# C-02_LvDDR3.net
KiCad netlist of a schematic drawn in Altium Designer
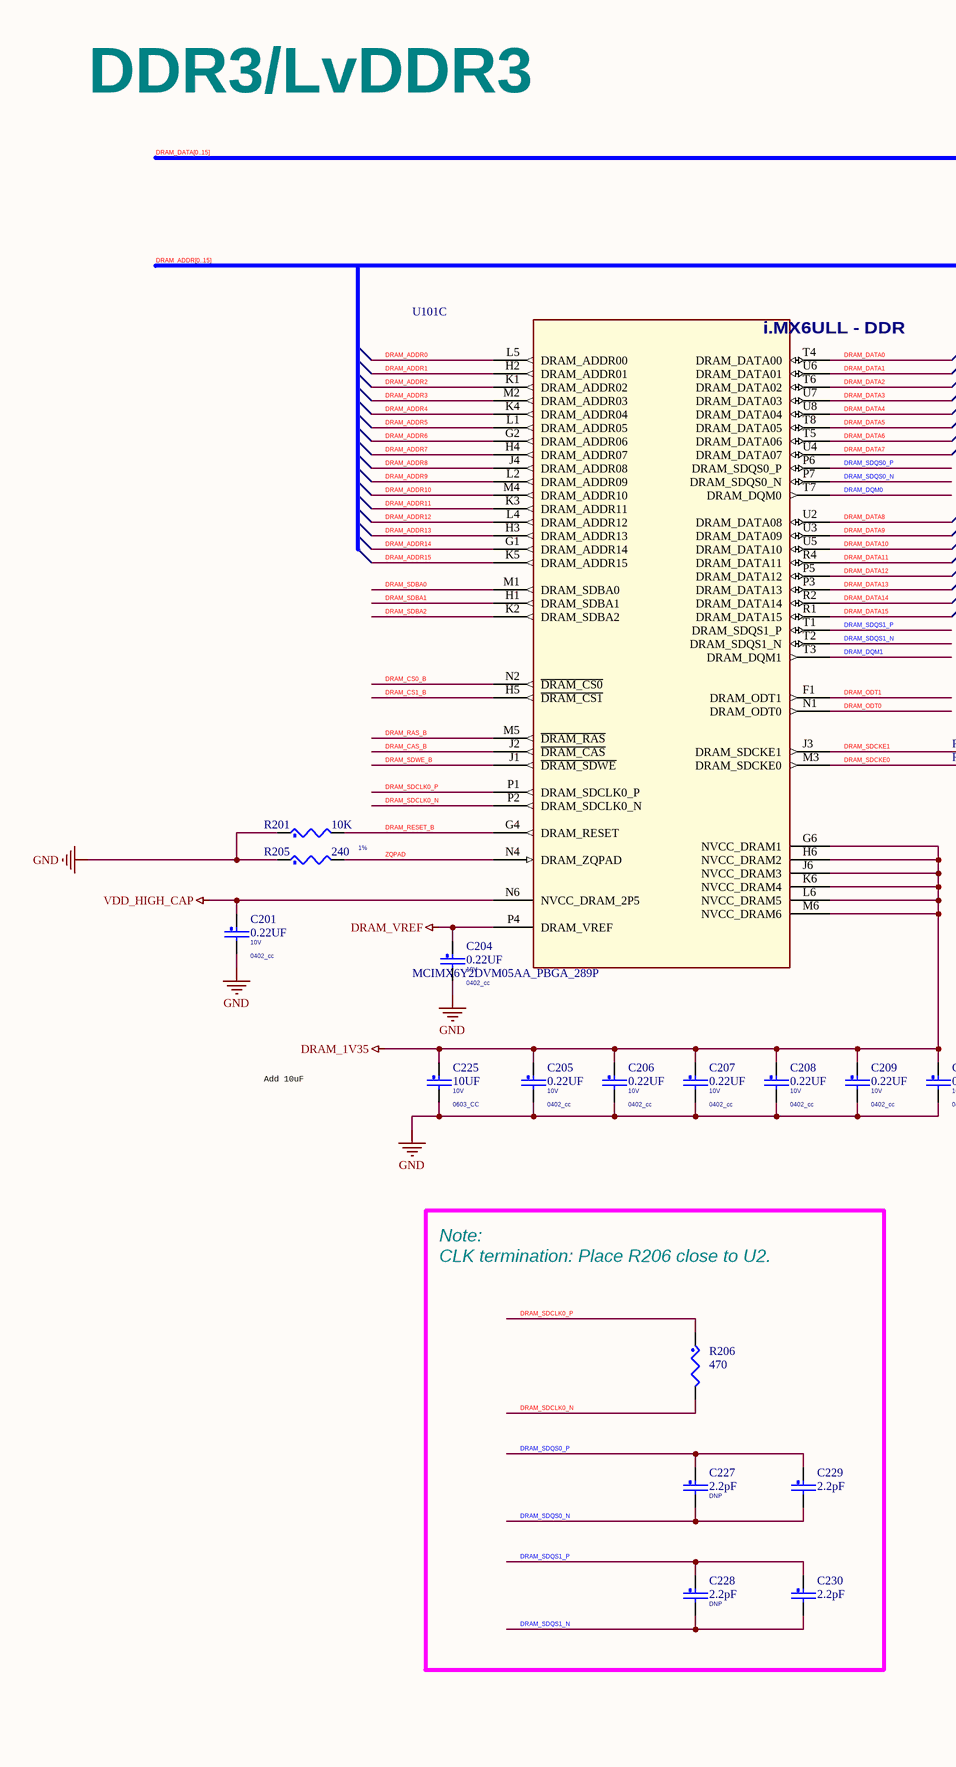
[diagram p0: C-02 LvDDR3.SchDoc, left]
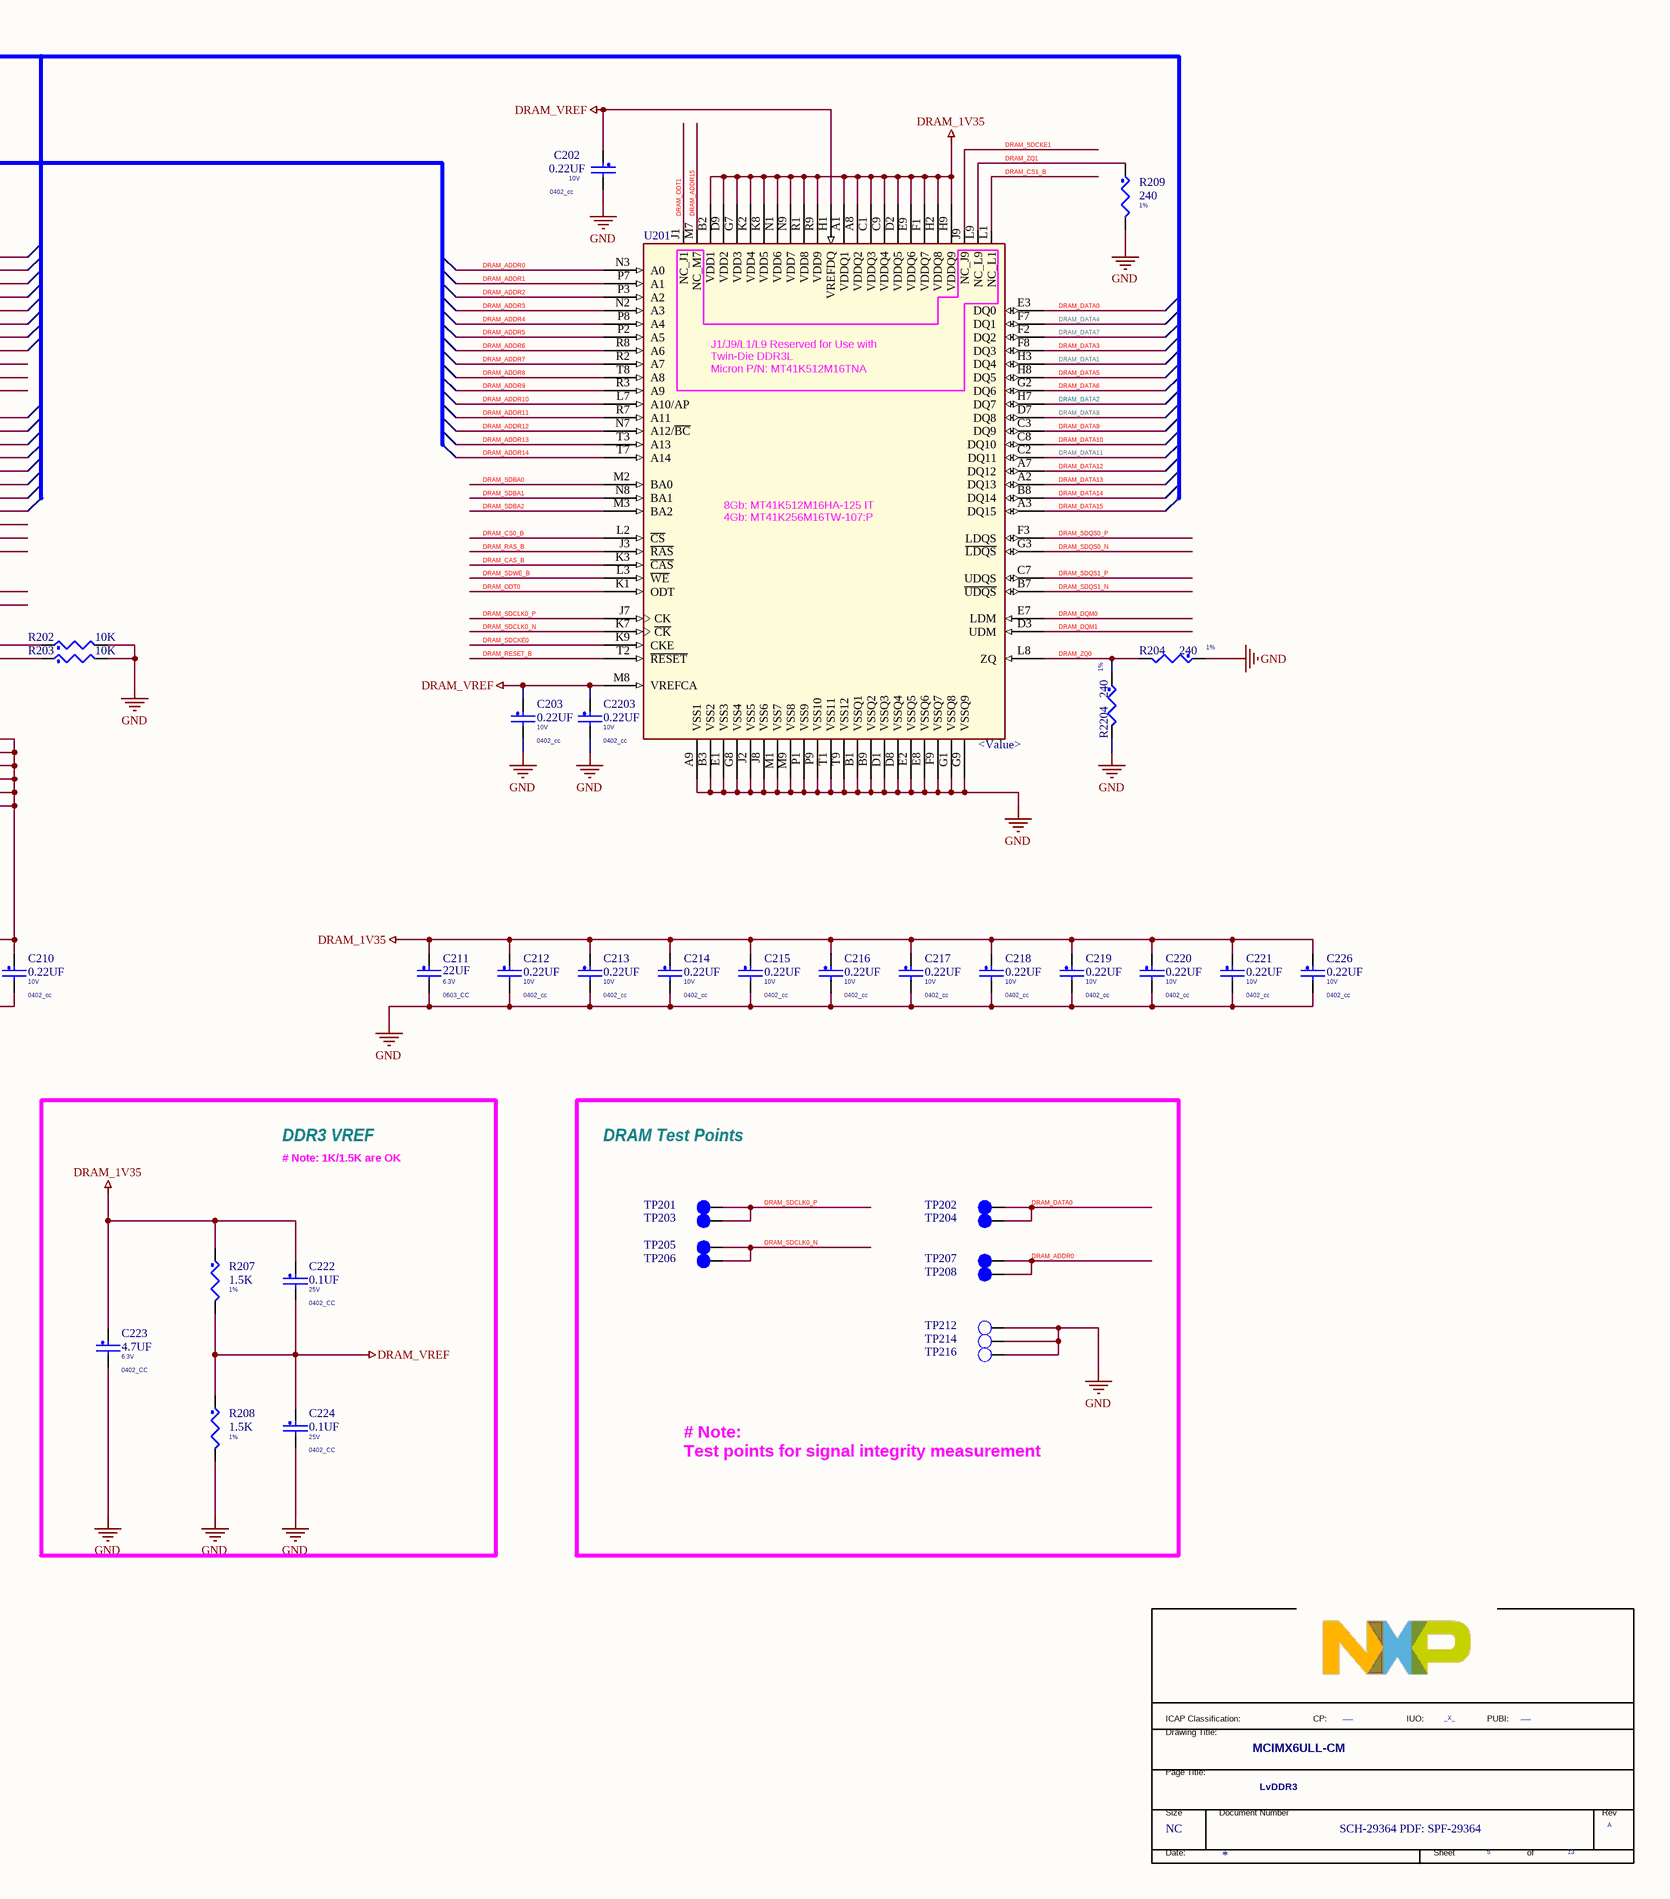
[diagram p1: C-02 LvDDR3.SchDoc, right]

(export (version "E")
  (design (tool "Eeschema 10.0.6"))
  (components
    (comp (ref "C201")
      (value "0.22UF")
      (footprint "C0402_H0.5mm")
      (description "CAP CER 0.22UF 10V 10% X5R 0402")
      (fields
        (field (name "TOLERANCE") "10%")
        (field (name "VOLTAGE") "10V")
        (field (name "PCB FOOTPRINT") "0402_cc")
      )
      (libsource (lib "*") (part "CAP_NP"))
    )
    (comp (ref "C202")
      (value "0.22UF")
      (footprint "C0402_H0.5mm")
      (description "CAP CER 0.22UF 10V 10% X5R 0402")
      (fields
        (field (name "VOLTAGE") "10V")
        (field (name "TOLERANCE") "10%")
        (field (name "PCB FOOTPRINT") "0402_cc")
      )
      (libsource (lib "*") (part "CAP_NP"))
    )
    (comp (ref "C203")
      (value "0.22UF")
      (footprint "C0402_H0.5mm")
      (description "CAP CER 0.22UF 10V 10% X5R 0402")
      (fields
        (field (name "VOLTAGE") "10V")
        (field (name "TOLERANCE") "10%")
        (field (name "PCB FOOTPRINT") "0402_cc")
      )
      (libsource (lib "*") (part "CAP_NP"))
    )
    (comp (ref "C204")
      (value "0.22UF")
      (footprint "C0402_H0.5mm")
      (description "CAP CER 0.22UF 10V 10% X5R 0402")
      (fields
        (field (name "TOLERANCE") "10%")
        (field (name "VOLTAGE") "10V")
        (field (name "PCB FOOTPRINT") "0402_cc")
      )
      (libsource (lib "*") (part "CAP_NP"))
    )
    (comp (ref "C205")
      (value "0.22UF")
      (footprint "C0402_H0.5mm")
      (description "CAP CER 0.22UF 10V 10% X5R 0402")
      (fields
        (field (name "VOLTAGE") "10V")
        (field (name "TOLERANCE") "10%")
        (field (name "PCB FOOTPRINT") "0402_cc")
      )
      (libsource (lib "*") (part "CAP_NP"))
    )
    (comp (ref "C206")
      (value "0.22UF")
      (footprint "C0402_H0.5mm")
      (description "CAP CER 0.22UF 10V 10% X5R 0402")
      (fields
        (field (name "VOLTAGE") "10V")
        (field (name "TOLERANCE") "10%")
        (field (name "PCB FOOTPRINT") "0402_cc")
      )
      (libsource (lib "*") (part "CAP_NP"))
    )
    (comp (ref "C207")
      (value "0.22UF")
      (footprint "C0402_H0.5mm")
      (description "CAP CER 0.22UF 10V 10% X5R 0402")
      (fields
        (field (name "VOLTAGE") "10V")
        (field (name "TOLERANCE") "10%")
        (field (name "PCB FOOTPRINT") "0402_cc")
      )
      (libsource (lib "*") (part "CAP_NP"))
    )
    (comp (ref "C208")
      (value "0.22UF")
      (footprint "C0402_H0.5mm")
      (description "CAP CER 0.22UF 10V 10% X5R 0402")
      (fields
        (field (name "VOLTAGE") "10V")
        (field (name "TOLERANCE") "10%")
        (field (name "PCB FOOTPRINT") "0402_cc")
      )
      (libsource (lib "*") (part "CAP_NP"))
    )
    (comp (ref "C209")
      (value "0.22UF")
      (footprint "C0402_H0.5mm")
      (description "CAP CER 0.22UF 10V 10% X5R 0402")
      (fields
        (field (name "VOLTAGE") "10V")
        (field (name "TOLERANCE") "10%")
        (field (name "PCB FOOTPRINT") "0402_cc")
      )
      (libsource (lib "*") (part "CAP_NP"))
    )
    (comp (ref "C210")
      (value "0.22UF")
      (footprint "C0402_H0.5mm")
      (description "CAP CER 0.22UF 10V 10% X5R 0402")
      (fields
        (field (name "TOLERANCE") "10%")
        (field (name "VOLTAGE") "10V")
        (field (name "PCB FOOTPRINT") "0402_cc")
      )
      (libsource (lib "*") (part "CAP_NP"))
    )
    (comp (ref "C211")
      (value "22UF")
      (footprint "C0603_H0.8mm")
      (description "CAP CER 22UF 6.3V 20% X5R 0603")
      (fields
        (field (name "VOLTAGE") "6.3V")
        (field (name "TOLERANCE") "20%")
        (field (name "VOLTAGE RATING") "6.3V")
        (field (name "PCB FOOTPRINT") "0603_CC")
      )
      (libsource (lib "*") (part "CAP_NP"))
    )
    (comp (ref "C212")
      (value "0.22UF")
      (footprint "C0402_H0.5mm")
      (description "CAP CER 0.22UF 10V 10% X5R 0402")
      (fields
        (field (name "VOLTAGE") "10V")
        (field (name "TOLERANCE") "10%")
        (field (name "PCB FOOTPRINT") "0402_cc")
      )
      (libsource (lib "*") (part "CAP_NP"))
    )
    (comp (ref "C213")
      (value "0.22UF")
      (footprint "C0402_H0.5mm")
      (description "CAP CER 0.22UF 10V 10% X5R 0402")
      (fields
        (field (name "VOLTAGE") "10V")
        (field (name "TOLERANCE") "10%")
        (field (name "PCB FOOTPRINT") "0402_cc")
      )
      (libsource (lib "*") (part "CAP_NP"))
    )
    (comp (ref "C214")
      (value "0.22UF")
      (footprint "C0402_H0.5mm")
      (description "CAP CER 0.22UF 10V 10% X5R 0402")
      (fields
        (field (name "VOLTAGE") "10V")
        (field (name "TOLERANCE") "10%")
        (field (name "PCB FOOTPRINT") "0402_cc")
      )
      (libsource (lib "*") (part "CAP_NP"))
    )
    (comp (ref "C215")
      (value "0.22UF")
      (footprint "C0402_H0.5mm")
      (description "CAP CER 0.22UF 10V 10% X5R 0402")
      (fields
        (field (name "VOLTAGE") "10V")
        (field (name "TOLERANCE") "10%")
        (field (name "PCB FOOTPRINT") "0402_cc")
      )
      (libsource (lib "*") (part "CAP_NP"))
    )
    (comp (ref "C216")
      (value "0.22UF")
      (footprint "C0402_H0.5mm")
      (description "CAP CER 0.22UF 10V 10% X5R 0402")
      (fields
        (field (name "VOLTAGE") "10V")
        (field (name "TOLERANCE") "10%")
        (field (name "PCB FOOTPRINT") "0402_cc")
      )
      (libsource (lib "*") (part "CAP_NP"))
    )
    (comp (ref "C217")
      (value "0.22UF")
      (footprint "C0402_H0.5mm")
      (description "CAP CER 0.22UF 10V 10% X5R 0402")
      (fields
        (field (name "TOLERANCE") "10%")
        (field (name "VOLTAGE") "10V")
        (field (name "PCB FOOTPRINT") "0402_cc")
      )
      (libsource (lib "*") (part "CAP_NP"))
    )
    (comp (ref "C218")
      (value "0.22UF")
      (footprint "C0402_H0.5mm")
      (description "CAP CER 0.22UF 10V 10% X5R 0402")
      (fields
        (field (name "TOLERANCE") "10%")
        (field (name "VOLTAGE") "10V")
        (field (name "PCB FOOTPRINT") "0402_cc")
      )
      (libsource (lib "*") (part "CAP_NP"))
    )
    (comp (ref "C219")
      (value "0.22UF")
      (footprint "C0402_H0.5mm")
      (description "CAP CER 0.22UF 10V 10% X5R 0402")
      (fields
        (field (name "TOLERANCE") "10%")
        (field (name "VOLTAGE") "10V")
        (field (name "PCB FOOTPRINT") "0402_cc")
      )
      (libsource (lib "*") (part "CAP_NP"))
    )
    (comp (ref "C220")
      (value "0.22UF")
      (footprint "C0402_H0.5mm")
      (description "CAP CER 0.22UF 10V 10% X5R 0402")
      (fields
        (field (name "TOLERANCE") "10%")
        (field (name "VOLTAGE") "10V")
        (field (name "PCB FOOTPRINT") "0402_cc")
      )
      (libsource (lib "*") (part "CAP_NP"))
    )
    (comp (ref "C221")
      (value "0.22UF")
      (footprint "C0402_H0.5mm")
      (description "CAP CER 0.22UF 10V 10% X5R 0402")
      (fields
        (field (name "TOLERANCE") "10%")
        (field (name "VOLTAGE") "10V")
        (field (name "PCB FOOTPRINT") "0402_cc")
      )
      (libsource (lib "*") (part "CAP_NP"))
    )
    (comp (ref "C222")
      (value "0.1UF")
      (footprint "C0402_H0.5mm")
      (description "CAP CER 0.1UF 25V 10% X5R 0402")
      (fields
        (field (name "VOLTAGE") "25V")
        (field (name "TOLERANCE") "10%")
        (field (name "PCB FOOTPRINT") "0402_CC")
      )
      (libsource (lib "*") (part "CAP_NP"))
    )
    (comp (ref "C223")
      (value "4.7UF")
      (footprint "C0402_H0.5mm")
      (description "CAP CER 4.7UF 6.3V 20% X5R 0402")
      (fields
        (field (name "VOLTAGE") "6.3V")
        (field (name "VOLTAGE RATING") "6.3V")
        (field (name "TOLERANCE") "20%")
        (field (name "PCB FOOTPRINT") "0402_CC")
      )
      (libsource (lib "*") (part "CAP_NP"))
    )
    (comp (ref "C224")
      (value "0.1UF")
      (footprint "C0402_H0.5mm")
      (description "CAP CER 0.1UF 25V 10% X5R 0402")
      (fields
        (field (name "VOLTAGE") "25V")
        (field (name "TOLERANCE") "10%")
        (field (name "PCB FOOTPRINT") "0402_CC")
      )
      (libsource (lib "*") (part "CAP_NP"))
    )
    (comp (ref "C225")
      (value "10UF")
      (footprint "C0603_H0.8mm")
      (description "CAP CER 10UF 10V 20% X5R 0603")
      (fields (field (name "VOLTAGE") "10V") (field (name "PCB FOOTPRINT") "0603_CC"))
      (libsource (lib "*") (part "CAP_NP"))
    )
    (comp (ref "C226")
      (value "0.22UF")
      (footprint "C0402_H0.5mm")
      (description "CAP CER 0.22UF 10V 10% X5R 0402")
      (fields
        (field (name "PCB FOOTPRINT") "0402_cc")
        (field (name "VOLTAGE") "10V")
        (field (name "TOLERANCE") "10%")
      )
      (libsource (lib "*") (part "CAP_NP"))
    )
    (comp (ref "C227")
      (value "2.2pF")
      (footprint "C0402_H0.5mm")
      (description "CAP CER 2.2pF 50V 0.25pF C0G 0402")
      (fields
        (field (name "TOLERANCE") "11.36%")
        (field (name "ASSY_OPT") "DNP")
        (field (name "VOLTAGE") "50V")
      )
      (libsource (lib "*") (part "CAP_NP"))
    )
    (comp (ref "C228")
      (value "2.2pF")
      (footprint "C0402_H0.5mm")
      (description "CAP CER 2.2pF 50V 0.25pF C0G 0402")
      (fields
        (field (name "TOLERANCE") "11.36%")
        (field (name "ASSY_OPT") "DNP")
        (field (name "VOLTAGE") "50V")
      )
      (libsource (lib "*") (part "CAP_NP"))
    )
    (comp (ref "C229")
      (value "2.2pF")
      (footprint "C0402_H0.5mm")
      (description "CAP CER 2.2pF 50V 0.25pF C0G 0402")
      (fields (field (name "TOLERANCE") "11.36%") (field (name "VOLTAGE") "50V"))
      (libsource (lib "*") (part "CAP_NP"))
    )
    (comp (ref "C230")
      (value "2.2pF")
      (footprint "C0402_H0.5mm")
      (description "CAP CER 2.2pF 50V 0.25pF C0G 0402")
      (fields (field (name "TOLERANCE") "11.36%") (field (name "VOLTAGE") "50V"))
      (libsource (lib "*") (part "CAP_NP"))
    )
    (comp (ref "C2203")
      (value "0.22UF")
      (footprint "C0402_H0.5mm")
      (description "CAP CER 0.22UF 10V 10% X5R 0402")
      (fields
        (field (name "VOLTAGE") "10V")
        (field (name "TOLERANCE") "10%")
        (field (name "PCB FOOTPRINT") "0402_cc")
      )
      (libsource (lib "*") (part "CAP_NP"))
    )
    (comp (ref "R201")
      (value "10K")
      (footprint "R0402_H0.35mm")
      (description "RES MF 10K 1/16W 5% 0402")
      (fields (field (name "TOLERANCE") "5%"))
      (libsource (lib "*") (part "RES"))
    )
    (comp (ref "R202")
      (value "10K")
      (footprint "R0402_H0.35mm")
      (description "RES MF 10K 1/16W 5% 0402")
      (fields (field (name "TOLERANCE") "5%"))
      (libsource (lib "*") (part "RES"))
    )
    (comp (ref "R203")
      (value "10K")
      (footprint "R0402_H0.35mm")
      (description "RES MF 10K 1/16W 5% 0402")
      (fields (field (name "TOLERANCE") "5%"))
      (libsource (lib "*") (part "RES"))
    )
    (comp (ref "R204")
      (value "240")
      (footprint "R0402_H0.35mm")
      (description "RES MF 240 OHM 1/16W 1% 0402")
      (fields (field (name "TOLERANCE") "1%"))
      (libsource (lib "*") (part "RES"))
    )
    (comp (ref "R205")
      (value "240")
      (footprint "R0402_H0.35mm")
      (description "RES MF 240 OHM 1/16W 1% 0402")
      (fields (field (name "TOLERANCE") "1%"))
      (libsource (lib "*") (part "RES"))
    )
    (comp (ref "R206")
      (value "470")
      (footprint "R0402_H0.35mm")
      (description "RES MF 470 OHM 1/16W 5% 0402")
      (fields (field (name "TOLERANCE") "5%"))
      (libsource (lib "*") (part "RES"))
    )
    (comp (ref "R207")
      (value "1.5K")
      (footprint "R0402_H0.35mm")
      (description "RES MF 1.5K 1/16W 1% 0402")
      (fields (field (name "TOLERANCE") "1%"))
      (libsource (lib "*") (part "RES"))
    )
    (comp (ref "R208")
      (value "1.5K")
      (footprint "R0402_H0.35mm")
      (description "RES MF 1.5K 1/16W 1% 0402")
      (fields (field (name "TOLERANCE") "1%"))
      (libsource (lib "*") (part "RES"))
    )
    (comp (ref "R209")
      (value "240")
      (footprint "R0402_H0.35mm")
      (description "RES MF 240 OHM 1/16W 1% 0402")
      (fields (field (name "TOLERANCE") "1%"))
      (libsource (lib "*") (part "RES"))
    )
    (comp (ref "R2204")
      (value "240")
      (footprint "R0402_H0.35mm")
      (description "RES MF 240 OHM 1/16W 1% 0402")
      (fields (field (name "TOLERANCE") "1%"))
      (libsource (lib "*") (part "RES"))
    )
    (comp (ref "TP201")
      (value "TPAD_015")
      (footprint "TPAD_015")
      (description "TEST POINT PAD 15MIL DIA SMT, NO PART TO ORDER")
      (libsource (lib "*") (part "TESTLOOP"))
    )
    (comp (ref "TP202")
      (value "TPAD_015")
      (footprint "TPAD_015")
      (description "TEST POINT PAD 15MIL DIA SMT, NO PART TO ORDER")
      (libsource (lib "*") (part "TESTLOOP"))
    )
    (comp (ref "TP203")
      (value "TPAD_015")
      (footprint "TPAD_015")
      (description "TEST POINT PAD 15MIL DIA SMT, NO PART TO ORDER")
      (libsource (lib "*") (part "TESTLOOP"))
    )
    (comp (ref "TP204")
      (value "TPAD_015")
      (footprint "TPAD_015")
      (description "TEST POINT PAD 15MIL DIA SMT, NO PART TO ORDER")
      (libsource (lib "*") (part "TESTLOOP"))
    )
    (comp (ref "TP205")
      (value "TPAD_015")
      (footprint "TPAD_015")
      (description "TEST POINT PAD 15MIL DIA SMT, NO PART TO ORDER")
      (libsource (lib "*") (part "TESTLOOP"))
    )
    (comp (ref "TP206")
      (value "TPAD_015")
      (footprint "TPAD_015")
      (description "TEST POINT PAD 15MIL DIA SMT, NO PART TO ORDER")
      (libsource (lib "*") (part "TESTLOOP"))
    )
    (comp (ref "TP207")
      (value "TPAD_015")
      (footprint "TPAD_015")
      (description "TEST POINT PAD 15MIL DIA SMT, NO PART TO ORDER")
      (libsource (lib "*") (part "TESTLOOP"))
    )
    (comp (ref "TP208")
      (value "TPAD_015")
      (footprint "TPAD_015")
      (description "TEST POINT PAD 15MIL DIA SMT, NO PART TO ORDER")
      (libsource (lib "*") (part "TESTLOOP"))
    )
    (comp (ref "TP212")
      (value "TP_35MIL")
      (footprint "TPAD_035")
      (description "TEST POINT PAD .035 SMT, no part to order")
      (libsource (lib "*") (part "T POINT R"))
    )
    (comp (ref "TP214")
      (value "TP_35MIL")
      (footprint "TPAD_035")
      (description "TEST POINT PAD .035 SMT, no part to order")
      (libsource (lib "*") (part "T POINT R"))
    )
    (comp (ref "TP216")
      (value "TP_35MIL")
      (footprint "TPAD_035")
      (description "TEST POINT PAD .035 SMT, no part to order")
      (libsource (lib "*") (part "T POINT R"))
    )
    (comp (ref "U101")
      (value "MCIMX6Y2DVM05AA_PBGA_289P")
      (footprint "BGA289_14x14mm")
      (libsource (lib "SCH-29364_a_Library") (part "MCIMX6Y2DVM05AA_PBGA_289P"))
    )
    (comp (ref "U201")
      (value "<Value>")
      (footprint "BGA96_8x14mm")
      (libsource (lib "SCH-29364_a_Library") (part "MT41J256M16RE_FBGA96"))
    )
  )
  (nets
    (net (code "1") (name "/DRAM_ADDR0") (class "Default")
      (node (ref "TP207") (pin "1") (pinfunction "Pin1_1") (pintype "passive"))
      (node (ref "TP208") (pin "1") (pinfunction "Pin1_1") (pintype "passive"))
      (node (ref "U101") (pin "L5") (pinfunction "DRAM_ADDR00_L5") (pintype "output"))
      (node (ref "U201") (pin "N3") (pinfunction "A0_N3") (pintype "input"))
    )
    (net (code "2") (name "/DRAM_ADDR1") (class "Default")
      (node (ref "U101") (pin "H2") (pinfunction "DRAM_ADDR01_H2") (pintype "output"))
      (node (ref "U201") (pin "P7") (pinfunction "A1_P7") (pintype "input"))
    )
    (net (code "3") (name "/DRAM_ADDR2") (class "Default")
      (node (ref "U101") (pin "K1") (pinfunction "DRAM_ADDR02_K1") (pintype "output"))
      (node (ref "U201") (pin "P3") (pinfunction "A2_P3") (pintype "input"))
    )
    (net (code "4") (name "/DRAM_ADDR3") (class "Default")
      (node (ref "U101") (pin "M2") (pinfunction "DRAM_ADDR03_M2") (pintype "output"))
      (node (ref "U201") (pin "N2") (pinfunction "A3_N2") (pintype "input"))
    )
    (net (code "5") (name "/DRAM_ADDR4") (class "Default")
      (node (ref "U101") (pin "K4") (pinfunction "DRAM_ADDR04_K4") (pintype "output"))
      (node (ref "U201") (pin "P8") (pinfunction "A4_P8") (pintype "input"))
    )
    (net (code "6") (name "/DRAM_ADDR5") (class "Default")
      (node (ref "U101") (pin "L1") (pinfunction "DRAM_ADDR05_L1") (pintype "output"))
      (node (ref "U201") (pin "P2") (pinfunction "A5_P2") (pintype "input"))
    )
    (net (code "7") (name "/DRAM_ADDR6") (class "Default")
      (node (ref "U101") (pin "G2") (pinfunction "DRAM_ADDR06_G2") (pintype "output"))
      (node (ref "U201") (pin "R8") (pinfunction "A6_R8") (pintype "input"))
    )
    (net (code "8") (name "/DRAM_ADDR7") (class "Default")
      (node (ref "U101") (pin "H4") (pinfunction "DRAM_ADDR07_H4") (pintype "output"))
      (node (ref "U201") (pin "R2") (pinfunction "A7_R2") (pintype "input"))
    )
    (net (code "9") (name "/DRAM_ADDR8") (class "Default")
      (node (ref "U101") (pin "J4") (pinfunction "DRAM_ADDR08_J4") (pintype "output"))
      (node (ref "U201") (pin "T8") (pinfunction "A8_T8") (pintype "input"))
    )
    (net (code "10") (name "/DRAM_ADDR9") (class "Default")
      (node (ref "U101") (pin "L2") (pinfunction "DRAM_ADDR09_L2") (pintype "output"))
      (node (ref "U201") (pin "R3") (pinfunction "A9_R3") (pintype "input"))
    )
    (net (code "11") (name "/DRAM_ADDR10") (class "Default")
      (node (ref "U101") (pin "M4") (pinfunction "DRAM_ADDR10_M4") (pintype "output"))
      (node (ref "U201") (pin "L7") (pinfunction "A10/AP_L7") (pintype "input"))
    )
    (net (code "12") (name "/DRAM_ADDR11") (class "Default")
      (node (ref "U101") (pin "K3") (pinfunction "DRAM_ADDR11_K3") (pintype "output"))
      (node (ref "U201") (pin "R7") (pinfunction "A11_R7") (pintype "input"))
    )
    (net (code "13") (name "/DRAM_ADDR12") (class "Default")
      (node (ref "U101") (pin "L4") (pinfunction "DRAM_ADDR12_L4") (pintype "output"))
      (node (ref "U201") (pin "N7") (pinfunction "A12/~{BC}_N7") (pintype "input"))
    )
    (net (code "14") (name "/DRAM_ADDR13") (class "Default")
      (node (ref "U101") (pin "H3") (pinfunction "DRAM_ADDR13_H3") (pintype "output"))
      (node (ref "U201") (pin "T3") (pinfunction "A13_T3") (pintype "input"))
    )
    (net (code "15") (name "/DRAM_ADDR14") (class "Default")
      (node (ref "U101") (pin "G1") (pinfunction "DRAM_ADDR14_G1") (pintype "output"))
      (node (ref "U201") (pin "T7") (pinfunction "A14_T7") (pintype "input"))
    )
    (net (code "16") (name "/DRAM_ADDR15") (class "Default")
      (node (ref "U101") (pin "K5") (pinfunction "DRAM_ADDR15_K5") (pintype "output"))
      (node (ref "U201") (pin "M7") (pinfunction "NC_M7_M7") (pintype "passive"))
    )
    (net (code "18") (name "/DRAM_CAS_B") (class "Default")
      (node (ref "U101") (pin "J2") (pinfunction "~{DRAM_CAS}_J2") (pintype "output"))
      (node (ref "U201") (pin "K3") (pinfunction "~{CAS}_K3") (pintype "input"))
    )
    (net (code "19") (name "/DRAM_CS0_B") (class "Default")
      (node (ref "U101") (pin "N2") (pinfunction "~{DRAM_CS0}_N2") (pintype "output"))
      (node (ref "U201") (pin "L2") (pinfunction "~{CS}_L2") (pintype "input"))
    )
    (net (code "20") (name "/DRAM_CS1_B") (class "Default")
      (node (ref "U101") (pin "H5") (pinfunction "~{DRAM_CS1}_H5") (pintype "output"))
      (node (ref "U201") (pin "L1") (pinfunction "NC_L1_L1") (pintype "passive"))
    )
    (net (code "21") (name "/DRAM_DATA0") (class "Default")
      (node (ref "TP202") (pin "1") (pinfunction "Pin1_1") (pintype "passive"))
      (node (ref "TP204") (pin "1") (pinfunction "Pin1_1") (pintype "passive"))
      (node (ref "U101") (pin "T4") (pinfunction "DRAM_DATA00_T4") (pintype "bidirectional"))
      (node (ref "U201") (pin "E3") (pinfunction "DQ0_E3") (pintype "bidirectional"))
    )
    (net (code "22") (name "/DRAM_DATA1") (class "Default")
      (node (ref "U101") (pin "U6") (pinfunction "DRAM_DATA01_U6") (pintype "bidirectional"))
      (node (ref "U201") (pin "H3") (pinfunction "DQ4_H3") (pintype "bidirectional"))
    )
    (net (code "23") (name "/DRAM_DATA2") (class "Default")
      (node (ref "U101") (pin "T6") (pinfunction "DRAM_DATA02_T6") (pintype "bidirectional"))
      (node (ref "U201") (pin "H7") (pinfunction "DQ7_H7") (pintype "bidirectional"))
    )
    (net (code "24") (name "/DRAM_DATA3") (class "Default")
      (node (ref "U101") (pin "U7") (pinfunction "DRAM_DATA03_U7") (pintype "bidirectional"))
      (node (ref "U201") (pin "F8") (pinfunction "DQ3_F8") (pintype "bidirectional"))
    )
    (net (code "25") (name "/DRAM_DATA4") (class "Default")
      (node (ref "U101") (pin "U8") (pinfunction "DRAM_DATA04_U8") (pintype "bidirectional"))
      (node (ref "U201") (pin "F7") (pinfunction "DQ1_F7") (pintype "bidirectional"))
    )
    (net (code "26") (name "/DRAM_DATA5") (class "Default")
      (node (ref "U101") (pin "T8") (pinfunction "DRAM_DATA05_T8") (pintype "bidirectional"))
      (node (ref "U201") (pin "H8") (pinfunction "DQ5_H8") (pintype "bidirectional"))
    )
    (net (code "27") (name "/DRAM_DATA6") (class "Default")
      (node (ref "U101") (pin "T5") (pinfunction "DRAM_DATA06_T5") (pintype "bidirectional"))
      (node (ref "U201") (pin "G2") (pinfunction "DQ6_G2") (pintype "bidirectional"))
    )
    (net (code "28") (name "/DRAM_DATA7") (class "Default")
      (node (ref "U101") (pin "U4") (pinfunction "DRAM_DATA07_U4") (pintype "bidirectional"))
      (node (ref "U201") (pin "F2") (pinfunction "DQ2_F2") (pintype "bidirectional"))
    )
    (net (code "29") (name "/DRAM_DATA8") (class "Default")
      (node (ref "U101") (pin "U2") (pinfunction "DRAM_DATA08_U2") (pintype "bidirectional"))
      (node (ref "U201") (pin "D7") (pinfunction "DQ8_D7") (pintype "bidirectional"))
    )
    (net (code "30") (name "/DRAM_DATA9") (class "Default")
      (node (ref "U101") (pin "U3") (pinfunction "DRAM_DATA09_U3") (pintype "bidirectional"))
      (node (ref "U201") (pin "C3") (pinfunction "DQ9_C3") (pintype "bidirectional"))
    )
    (net (code "31") (name "/DRAM_DATA10") (class "Default")
      (node (ref "U101") (pin "U5") (pinfunction "DRAM_DATA10_U5") (pintype "bidirectional"))
      (node (ref "U201") (pin "C8") (pinfunction "DQ10_C8") (pintype "bidirectional"))
    )
    (net (code "32") (name "/DRAM_DATA11") (class "Default")
      (node (ref "U101") (pin "R4") (pinfunction "DRAM_DATA11_R4") (pintype "bidirectional"))
      (node (ref "U201") (pin "C2") (pinfunction "DQ11_C2") (pintype "bidirectional"))
    )
    (net (code "33") (name "/DRAM_DATA12") (class "Default")
      (node (ref "U101") (pin "P5") (pinfunction "DRAM_DATA12_P5") (pintype "bidirectional"))
      (node (ref "U201") (pin "A7") (pinfunction "DQ12_A7") (pintype "bidirectional"))
    )
    (net (code "34") (name "/DRAM_DATA13") (class "Default")
      (node (ref "U101") (pin "P3") (pinfunction "DRAM_DATA13_P3") (pintype "bidirectional"))
      (node (ref "U201") (pin "A2") (pinfunction "DQ13_A2") (pintype "bidirectional"))
    )
    (net (code "35") (name "/DRAM_DATA14") (class "Default")
      (node (ref "U101") (pin "R2") (pinfunction "DRAM_DATA14_R2") (pintype "bidirectional"))
      (node (ref "U201") (pin "B8") (pinfunction "DQ14_B8") (pintype "bidirectional"))
    )
    (net (code "36") (name "/DRAM_DATA15") (class "Default")
      (node (ref "U101") (pin "R1") (pinfunction "DRAM_DATA15_R1") (pintype "bidirectional"))
      (node (ref "U201") (pin "A3") (pinfunction "DQ15_A3") (pintype "bidirectional"))
    )
    (net (code "38") (name "/DRAM_DQM0") (class "Default")
      (node (ref "U101") (pin "T7") (pinfunction "DRAM_DQM0_T7") (pintype "output"))
      (node (ref "U201") (pin "E7") (pinfunction "LDM_E7") (pintype "input"))
    )
    (net (code "39") (name "/DRAM_DQM1") (class "Default")
      (node (ref "U101") (pin "T3") (pinfunction "DRAM_DQM1_T3") (pintype "output"))
      (node (ref "U201") (pin "D3") (pinfunction "UDM_D3") (pintype "input"))
    )
    (net (code "40") (name "/DRAM_ODT0") (class "Default")
      (node (ref "U101") (pin "N1") (pinfunction "DRAM_ODT0_N1") (pintype "output"))
      (node (ref "U201") (pin "K1") (pinfunction "ODT_K1") (pintype "input"))
    )
    (net (code "41") (name "/DRAM_ODT1") (class "Default")
      (node (ref "U101") (pin "F1") (pinfunction "DRAM_ODT1_F1") (pintype "output"))
      (node (ref "U201") (pin "J1") (pinfunction "NC_J1_J1") (pintype "passive"))
    )
    (net (code "42") (name "/DRAM_RAS_B") (class "Default")
      (node (ref "U101") (pin "M5") (pinfunction "~{DRAM_RAS}_M5") (pintype "output"))
      (node (ref "U201") (pin "J3") (pinfunction "~{RAS}_J3") (pintype "input"))
    )
    (net (code "43") (name "/DRAM_RESET_B") (class "Default")
      (node (ref "R201") (pin "2") (pinfunction "2_2") (pintype "passive"))
      (node (ref "U101") (pin "G4") (pinfunction "DRAM_RESET_G4") (pintype "output"))
      (node (ref "U201") (pin "T2") (pinfunction "~{RESET}_T2") (pintype "input"))
    )
    (net (code "44") (name "/DRAM_SDBA0") (class "Default")
      (node (ref "U101") (pin "M1") (pinfunction "DRAM_SDBA0_M1") (pintype "output"))
      (node (ref "U201") (pin "M2") (pinfunction "BA0_M2") (pintype "input"))
    )
    (net (code "45") (name "/DRAM_SDBA1") (class "Default")
      (node (ref "U101") (pin "H1") (pinfunction "DRAM_SDBA1_H1") (pintype "output"))
      (node (ref "U201") (pin "N8") (pinfunction "BA1_N8") (pintype "input"))
    )
    (net (code "46") (name "/DRAM_SDBA2") (class "Default")
      (node (ref "U101") (pin "K2") (pinfunction "DRAM_SDBA2_K2") (pintype "output"))
      (node (ref "U201") (pin "M3") (pinfunction "BA2_M3") (pintype "input"))
    )
    (net (code "47") (name "/DRAM_SDCKE0") (class "Default")
      (node (ref "R203") (pin "1") (pinfunction "1_1") (pintype "passive"))
      (node (ref "U101") (pin "M3") (pinfunction "DRAM_SDCKE0_M3") (pintype "output"))
      (node (ref "U201") (pin "K9") (pinfunction "CKE_K9") (pintype "input"))
    )
    (net (code "48") (name "/DRAM_SDCKE1") (class "Default")
      (node (ref "R202") (pin "1") (pinfunction "1_1") (pintype "passive"))
      (node (ref "U101") (pin "J3") (pinfunction "DRAM_SDCKE1_J3") (pintype "output"))
      (node (ref "U201") (pin "J9") (pinfunction "NC_J9_J9") (pintype "passive"))
    )
    (net (code "49") (name "/DRAM_SDCLK0_N") (class "Default")
      (node (ref "R206") (pin "2") (pinfunction "2_2") (pintype "passive"))
      (node (ref "TP205") (pin "1") (pinfunction "Pin1_1") (pintype "passive"))
      (node (ref "TP206") (pin "1") (pinfunction "Pin1_1") (pintype "passive"))
      (node (ref "U101") (pin "P2") (pinfunction "DRAM_SDCLK0_N_P2") (pintype "output"))
      (node (ref "U201") (pin "K7") (pinfunction "~{CK}_K7") (pintype "input"))
    )
    (net (code "50") (name "/DRAM_SDCLK0_P") (class "Default")
      (node (ref "R206") (pin "1") (pinfunction "1_1") (pintype "passive"))
      (node (ref "TP201") (pin "1") (pinfunction "Pin1_1") (pintype "passive"))
      (node (ref "TP203") (pin "1") (pinfunction "Pin1_1") (pintype "passive"))
      (node (ref "U101") (pin "P1") (pinfunction "DRAM_SDCLK0_P_P1") (pintype "output"))
      (node (ref "U201") (pin "J7") (pinfunction "CK_J7") (pintype "input"))
    )
    (net (code "51") (name "/DRAM_SDQS0_N") (class "Default")
      (node (ref "C227") (pin "2") (pinfunction "2_2") (pintype "passive"))
      (node (ref "C229") (pin "2") (pinfunction "2_2") (pintype "passive"))
      (node (ref "U101") (pin "P7") (pinfunction "DRAM_SDQS0_N_P7") (pintype "bidirectional"))
      (node (ref "U201") (pin "G3") (pinfunction "~{LDQS}_G3") (pintype "bidirectional"))
    )
    (net (code "52") (name "/DRAM_SDQS0_P") (class "Default")
      (node (ref "C227") (pin "1") (pinfunction "1_1") (pintype "passive"))
      (node (ref "C229") (pin "1") (pinfunction "1_1") (pintype "passive"))
      (node (ref "U101") (pin "P6") (pinfunction "DRAM_SDQS0_P_P6") (pintype "bidirectional"))
      (node (ref "U201") (pin "F3") (pinfunction "LDQS_F3") (pintype "bidirectional"))
    )
    (net (code "53") (name "/DRAM_SDQS1_N") (class "Default")
      (node (ref "C228") (pin "2") (pinfunction "2_2") (pintype "passive"))
      (node (ref "C230") (pin "2") (pinfunction "2_2") (pintype "passive"))
      (node (ref "U101") (pin "T2") (pinfunction "DRAM_SDQS1_N_T2") (pintype "bidirectional"))
      (node (ref "U201") (pin "B7") (pinfunction "~{UDQS}_B7") (pintype "bidirectional"))
    )
    (net (code "54") (name "/DRAM_SDQS1_P") (class "Default")
      (node (ref "C228") (pin "1") (pinfunction "1_1") (pintype "passive"))
      (node (ref "C230") (pin "1") (pinfunction "1_1") (pintype "passive"))
      (node (ref "U101") (pin "T1") (pinfunction "DRAM_SDQS1_P_T1") (pintype "bidirectional"))
      (node (ref "U201") (pin "C7") (pinfunction "UDQS_C7") (pintype "bidirectional"))
    )
    (net (code "55") (name "/DRAM_SDWE_B") (class "Default")
      (node (ref "U101") (pin "J1") (pinfunction "~{DRAM_SDWE}_J1") (pintype "output"))
      (node (ref "U201") (pin "L3") (pinfunction "~{WE}_L3") (pintype "input"))
    )
    (net (code "56") (name "/DRAM_ZQ0") (class "Default")
      (node (ref "R204") (pin "2") (pinfunction "2_2") (pintype "passive"))
      (node (ref "R2204") (pin "1") (pinfunction "1_1") (pintype "passive"))
      (node (ref "U201") (pin "L8") (pinfunction "ZQ_L8") (pintype "input"))
    )
    (net (code "57") (name "/DRAM_ZQ1") (class "Default")
      (node (ref "R209") (pin "1") (pinfunction "1_1") (pintype "passive"))
      (node (ref "U201") (pin "L9") (pinfunction "NC_L9_L9") (pintype "passive"))
    )
    (net (code "58") (name "/ZQPAD") (class "Default")
      (node (ref "R205") (pin "2") (pinfunction "2_2") (pintype "passive"))
      (node (ref "U101") (pin "N4") (pinfunction "DRAM_ZQPAD_N4") (pintype "input"))
    )
    (net (code "59") (name "DRAM_1V35") (class "Default")
      (node (ref "C205") (pin "1") (pinfunction "1_1") (pintype "passive"))
      (node (ref "C206") (pin "1") (pinfunction "1_1") (pintype "passive"))
      (node (ref "C207") (pin "1") (pinfunction "1_1") (pintype "passive"))
      (node (ref "C208") (pin "1") (pinfunction "1_1") (pintype "passive"))
      (node (ref "C209") (pin "1") (pinfunction "1_1") (pintype "passive"))
      (node (ref "C210") (pin "1") (pinfunction "1_1") (pintype "passive"))
      (node (ref "C211") (pin "1") (pinfunction "1_1") (pintype "passive"))
      (node (ref "C212") (pin "1") (pinfunction "1_1") (pintype "passive"))
      (node (ref "C213") (pin "1") (pinfunction "1_1") (pintype "passive"))
      (node (ref "C214") (pin "1") (pinfunction "1_1") (pintype "passive"))
      (node (ref "C215") (pin "1") (pinfunction "1_1") (pintype "passive"))
      (node (ref "C216") (pin "1") (pinfunction "1_1") (pintype "passive"))
      (node (ref "C217") (pin "1") (pinfunction "1_1") (pintype "passive"))
      (node (ref "C218") (pin "1") (pinfunction "1_1") (pintype "passive"))
      (node (ref "C219") (pin "1") (pinfunction "1_1") (pintype "passive"))
      (node (ref "C220") (pin "1") (pinfunction "1_1") (pintype "passive"))
      (node (ref "C221") (pin "1") (pinfunction "1_1") (pintype "passive"))
      (node (ref "C222") (pin "1") (pinfunction "1_1") (pintype "passive"))
      (node (ref "C223") (pin "1") (pinfunction "1_1") (pintype "passive"))
      (node (ref "C225") (pin "1") (pinfunction "1_1") (pintype "passive"))
      (node (ref "C226") (pin "1") (pinfunction "1_1") (pintype "passive"))
      (node (ref "R207") (pin "1") (pinfunction "1_1") (pintype "passive"))
      (node (ref "U101") (pin "G6") (pinfunction "NVCC_DRAM1_G6") (pintype "power_in"))
      (node (ref "U101") (pin "H6") (pinfunction "NVCC_DRAM2_H6") (pintype "power_in"))
      (node (ref "U101") (pin "J6") (pinfunction "NVCC_DRAM3_J6") (pintype "power_in"))
      (node (ref "U101") (pin "K6") (pinfunction "NVCC_DRAM4_K6") (pintype "power_in"))
      (node (ref "U101") (pin "L6") (pinfunction "NVCC_DRAM5_L6") (pintype "power_in"))
      (node (ref "U101") (pin "M6") (pinfunction "NVCC_DRAM6_M6") (pintype "power_in"))
      (node (ref "U201") (pin "A1") (pinfunction "VDDQ1_A1") (pintype "power_in"))
      (node (ref "U201") (pin "A8") (pinfunction "VDDQ2_A8") (pintype "power_in"))
      (node (ref "U201") (pin "B2") (pinfunction "VDD1_B2") (pintype "power_in"))
      (node (ref "U201") (pin "C1") (pinfunction "VDDQ3_C1") (pintype "power_in"))
      (node (ref "U201") (pin "C9") (pinfunction "VDDQ4_C9") (pintype "power_in"))
      (node (ref "U201") (pin "D2") (pinfunction "VDDQ5_D2") (pintype "power_in"))
      (node (ref "U201") (pin "D9") (pinfunction "VDD2_D9") (pintype "power_in"))
      (node (ref "U201") (pin "E9") (pinfunction "VDDQ6_E9") (pintype "power_in"))
      (node (ref "U201") (pin "F1") (pinfunction "VDDQ7_F1") (pintype "power_in"))
      (node (ref "U201") (pin "G7") (pinfunction "VDD3_G7") (pintype "power_in"))
      (node (ref "U201") (pin "H2") (pinfunction "VDDQ8_H2") (pintype "power_in"))
      (node (ref "U201") (pin "H9") (pinfunction "VDDQ9_H9") (pintype "power_in"))
      (node (ref "U201") (pin "K2") (pinfunction "VDD4_K2") (pintype "power_in"))
      (node (ref "U201") (pin "K8") (pinfunction "VDD5_K8") (pintype "power_in"))
      (node (ref "U201") (pin "N1") (pinfunction "VDD6_N1") (pintype "power_in"))
      (node (ref "U201") (pin "N9") (pinfunction "VDD7_N9") (pintype "power_in"))
      (node (ref "U201") (pin "R1") (pinfunction "VDD8_R1") (pintype "power_in"))
      (node (ref "U201") (pin "R9") (pinfunction "VDD9_R9") (pintype "power_in"))
    )
    (net (code "60") (name "DRAM_VREF") (class "Default")
      (node (ref "C202") (pin "1") (pinfunction "1_1") (pintype "passive"))
      (node (ref "C203") (pin "1") (pinfunction "1_1") (pintype "passive"))
      (node (ref "C204") (pin "1") (pinfunction "1_1") (pintype "passive"))
      (node (ref "C2203") (pin "1") (pinfunction "1_1") (pintype "passive"))
      (node (ref "C222") (pin "2") (pinfunction "2_2") (pintype "passive"))
      (node (ref "C224") (pin "1") (pinfunction "1_1") (pintype "passive"))
      (node (ref "R207") (pin "2") (pinfunction "2_2") (pintype "passive"))
      (node (ref "R208") (pin "1") (pinfunction "1_1") (pintype "passive"))
      (node (ref "U101") (pin "P4") (pinfunction "DRAM_VREF_P4") (pintype "power_in"))
      (node (ref "U201") (pin "H1") (pinfunction "VREFDQ_H1") (pintype "input"))
      (node (ref "U201") (pin "M8") (pinfunction "VREFCA_M8") (pintype "input"))
    )
    (net (code "61") (name "GND") (class "Default")
      (node (ref "C201") (pin "2") (pinfunction "2_2") (pintype "passive"))
      (node (ref "C202") (pin "2") (pinfunction "2_2") (pintype "passive"))
      (node (ref "C203") (pin "2") (pinfunction "2_2") (pintype "passive"))
      (node (ref "C204") (pin "2") (pinfunction "2_2") (pintype "passive"))
      (node (ref "C205") (pin "2") (pinfunction "2_2") (pintype "passive"))
      (node (ref "C206") (pin "2") (pinfunction "2_2") (pintype "passive"))
      (node (ref "C207") (pin "2") (pinfunction "2_2") (pintype "passive"))
      (node (ref "C208") (pin "2") (pinfunction "2_2") (pintype "passive"))
      (node (ref "C209") (pin "2") (pinfunction "2_2") (pintype "passive"))
      (node (ref "C210") (pin "2") (pinfunction "2_2") (pintype "passive"))
      (node (ref "C211") (pin "2") (pinfunction "2_2") (pintype "passive"))
      (node (ref "C212") (pin "2") (pinfunction "2_2") (pintype "passive"))
      (node (ref "C213") (pin "2") (pinfunction "2_2") (pintype "passive"))
      (node (ref "C214") (pin "2") (pinfunction "2_2") (pintype "passive"))
      (node (ref "C215") (pin "2") (pinfunction "2_2") (pintype "passive"))
      (node (ref "C216") (pin "2") (pinfunction "2_2") (pintype "passive"))
      (node (ref "C217") (pin "2") (pinfunction "2_2") (pintype "passive"))
      (node (ref "C218") (pin "2") (pinfunction "2_2") (pintype "passive"))
      (node (ref "C219") (pin "2") (pinfunction "2_2") (pintype "passive"))
      (node (ref "C220") (pin "2") (pinfunction "2_2") (pintype "passive"))
      (node (ref "C2203") (pin "2") (pinfunction "2_2") (pintype "passive"))
      (node (ref "C221") (pin "2") (pinfunction "2_2") (pintype "passive"))
      (node (ref "C223") (pin "2") (pinfunction "2_2") (pintype "passive"))
      (node (ref "C224") (pin "2") (pinfunction "2_2") (pintype "passive"))
      (node (ref "C225") (pin "2") (pinfunction "2_2") (pintype "passive"))
      (node (ref "C226") (pin "2") (pinfunction "2_2") (pintype "passive"))
      (node (ref "R201") (pin "1") (pinfunction "1_1") (pintype "passive"))
      (node (ref "R202") (pin "2") (pinfunction "2_2") (pintype "passive"))
      (node (ref "R203") (pin "2") (pinfunction "2_2") (pintype "passive"))
      (node (ref "R204") (pin "1") (pinfunction "1_1") (pintype "passive"))
      (node (ref "R205") (pin "1") (pinfunction "1_1") (pintype "passive"))
      (node (ref "R208") (pin "2") (pinfunction "2_2") (pintype "passive"))
      (node (ref "R209") (pin "2") (pinfunction "2_2") (pintype "passive"))
      (node (ref "R2204") (pin "2") (pinfunction "2_2") (pintype "passive"))
      (node (ref "TP212") (pin "1") (pinfunction "TP_1") (pintype "passive"))
      (node (ref "TP214") (pin "1") (pinfunction "TP_1") (pintype "passive"))
      (node (ref "TP216") (pin "1") (pinfunction "TP_1") (pintype "passive"))
      (node (ref "U201") (pin "A9") (pinfunction "VSS1_A9") (pintype "power_in"))
      (node (ref "U201") (pin "B1") (pinfunction "VSSQ1_B1") (pintype "power_in"))
      (node (ref "U201") (pin "B3") (pinfunction "VSS2_B3") (pintype "power_in"))
      (node (ref "U201") (pin "B9") (pinfunction "VSSQ2_B9") (pintype "power_in"))
      (node (ref "U201") (pin "D1") (pinfunction "VSSQ3_D1") (pintype "power_in"))
      (node (ref "U201") (pin "D8") (pinfunction "VSSQ4_D8") (pintype "power_in"))
      (node (ref "U201") (pin "E1") (pinfunction "VSS3_E1") (pintype "power_in"))
      (node (ref "U201") (pin "E2") (pinfunction "VSSQ5_E2") (pintype "power_in"))
      (node (ref "U201") (pin "E8") (pinfunction "VSSQ6_E8") (pintype "power_in"))
      (node (ref "U201") (pin "F9") (pinfunction "VSSQ7_F9") (pintype "power_in"))
      (node (ref "U201") (pin "G1") (pinfunction "VSSQ8_G1") (pintype "power_in"))
      (node (ref "U201") (pin "G8") (pinfunction "VSS4_G8") (pintype "power_in"))
      (node (ref "U201") (pin "G9") (pinfunction "VSSQ9_G9") (pintype "power_in"))
      (node (ref "U201") (pin "J2") (pinfunction "VSS5_J2") (pintype "power_in"))
      (node (ref "U201") (pin "J8") (pinfunction "VSS6_J8") (pintype "power_in"))
      (node (ref "U201") (pin "M1") (pinfunction "VSS7_M1") (pintype "power_in"))
      (node (ref "U201") (pin "M9") (pinfunction "VSS8_M9") (pintype "power_in"))
      (node (ref "U201") (pin "P1") (pinfunction "VSS9_P1") (pintype "power_in"))
      (node (ref "U201") (pin "P9") (pinfunction "VSS10_P9") (pintype "power_in"))
      (node (ref "U201") (pin "T1") (pinfunction "VSS11_T1") (pintype "power_in"))
      (node (ref "U201") (pin "T9") (pinfunction "VSS12_T9") (pintype "power_in"))
    )
    (net (code "62") (name "VDD_HIGH_CAP") (class "Default")
      (node (ref "C201") (pin "1") (pinfunction "1_1") (pintype "passive"))
      (node (ref "U101") (pin "N6") (pinfunction "NVCC_DRAM_2P5_N6") (pintype "power_in"))
    )
  )
)
